# ESP_PGMRm.net
KiCad netlist of a schematic drawn in EAGLE
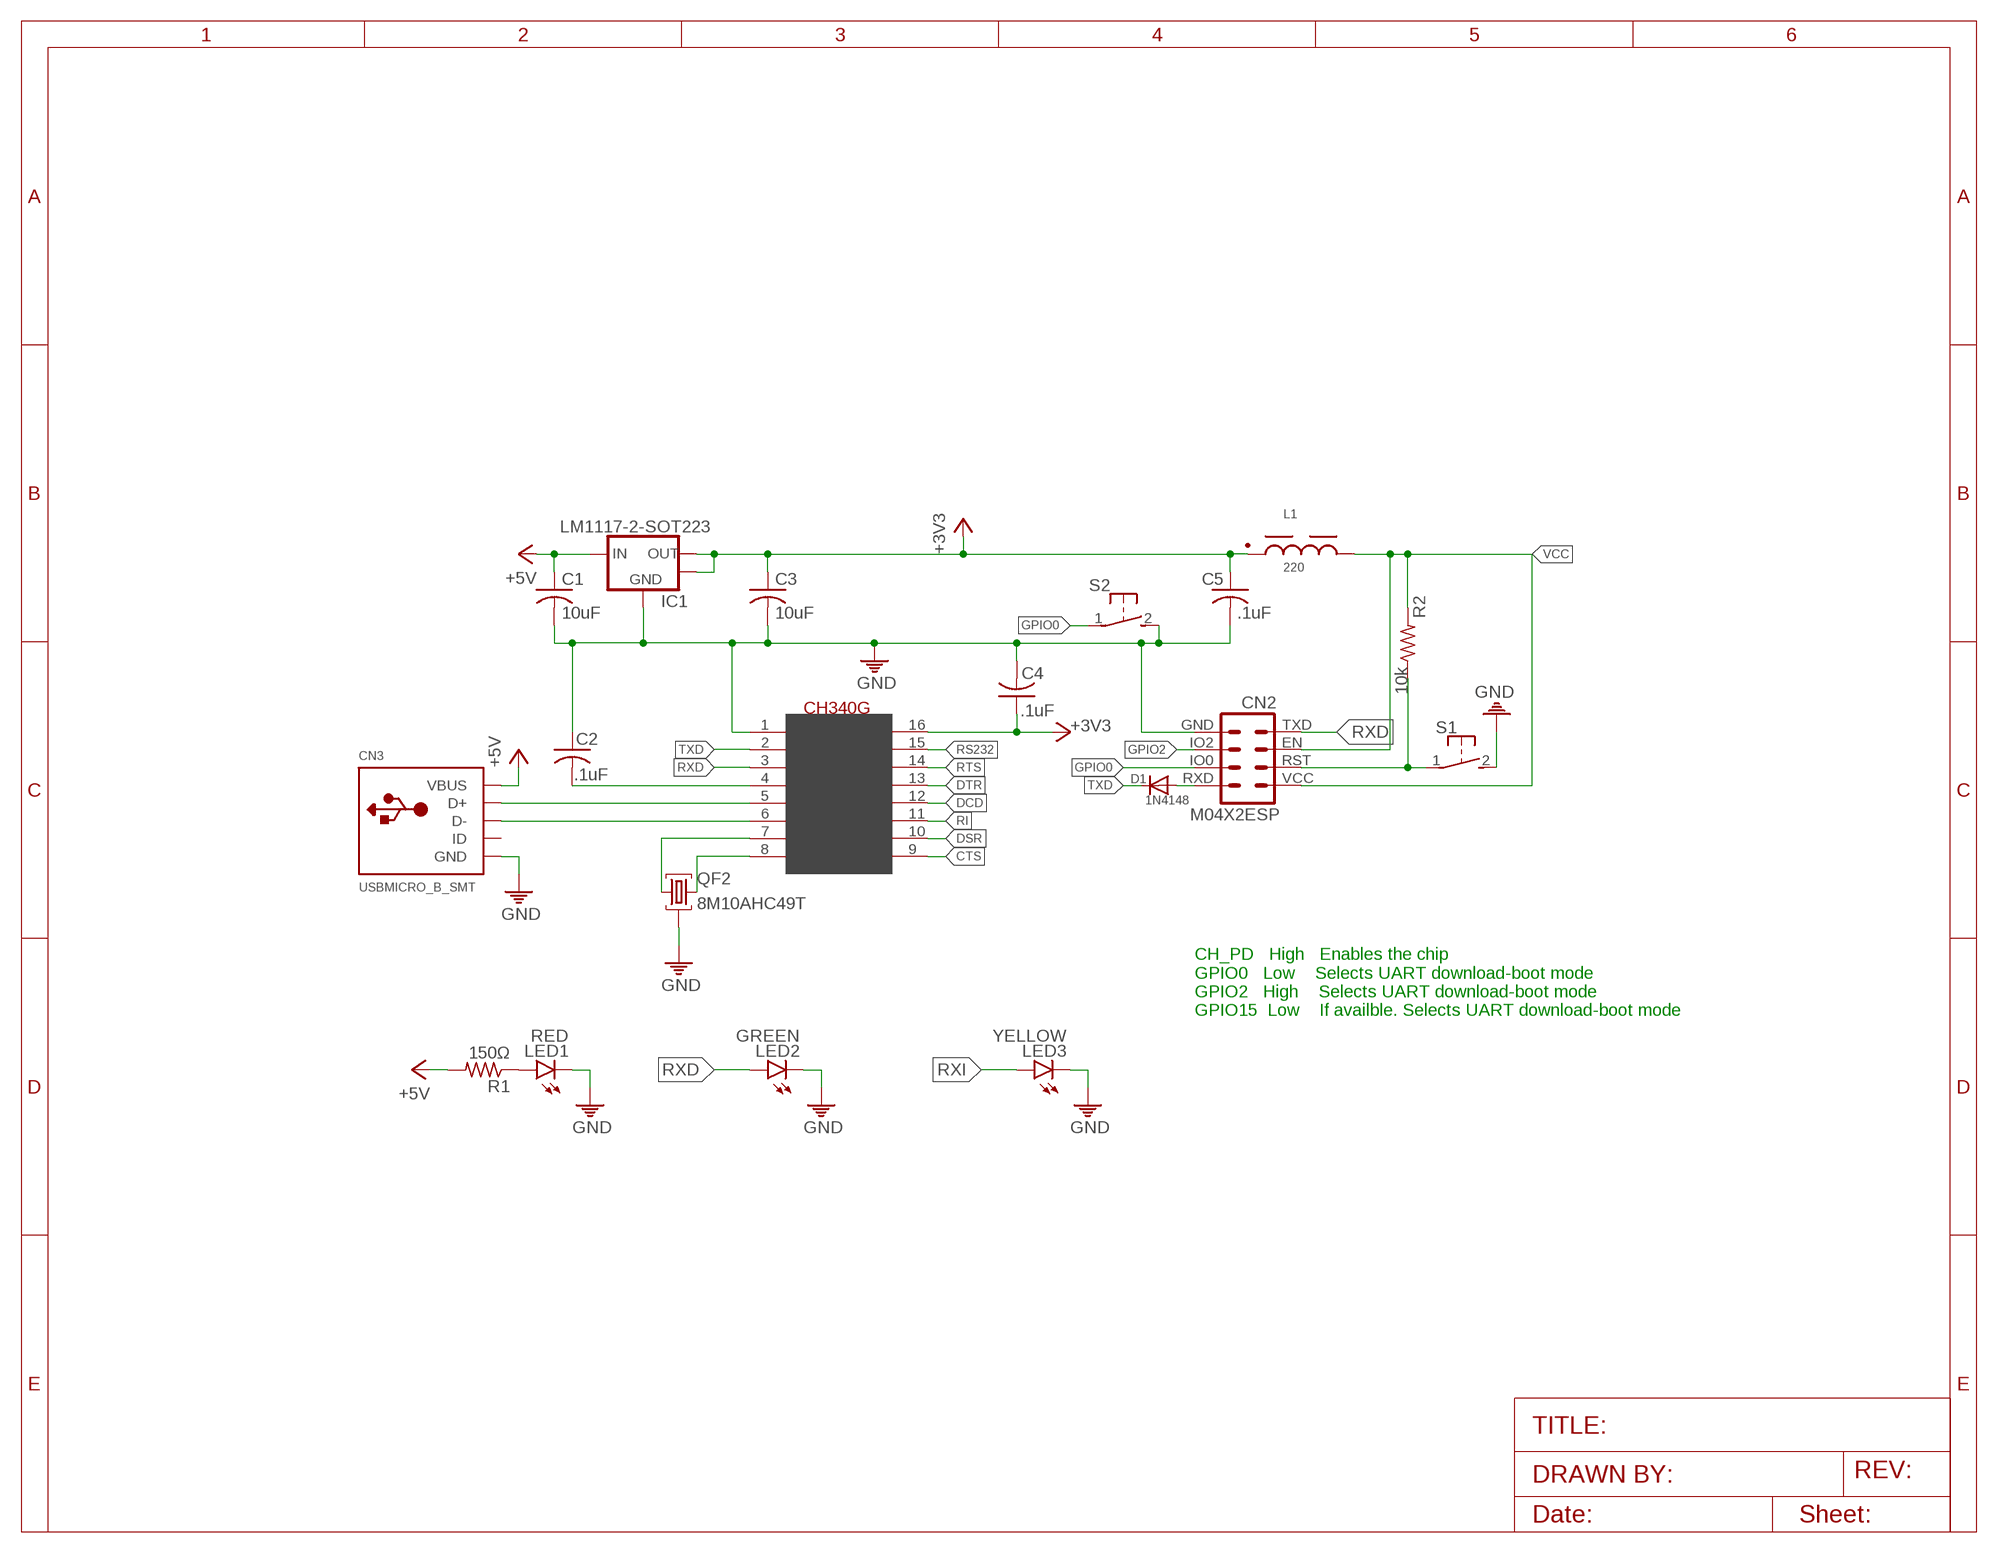
[diagram p0: schematic, sheet 1]

(export (version "E")
  (design (tool "Eeschema 10.0.6"))
  (components
    (comp (ref "C1")
      (value "10uF")
      (footprint "eagle-import:C0805")
      (libsource (lib "eagle-import") (part "C-USC0805"))
    )
    (comp (ref "C2")
      (value ".1uF")
      (footprint "eagle-import:C0805")
      (libsource (lib "eagle-import") (part "C-USC0805"))
    )
    (comp (ref "C3")
      (value "10uF")
      (footprint "eagle-import:C0805")
      (libsource (lib "eagle-import") (part "C-USC0805"))
    )
    (comp (ref "C4")
      (value ".1uF")
      (footprint "eagle-import:C0805")
      (libsource (lib "eagle-import") (part "C-USC0805"))
    )
    (comp (ref "C5")
      (value ".1uF")
      (footprint "eagle-import:C0805")
      (libsource (lib "eagle-import") (part "C-USC0805"))
    )
    (comp (ref "CN2")
      (value "M04X2ESP")
      (footprint "eagle-import:2X04-ESP")
      (libsource (lib "eagle-import") (part "M04X2ESP"))
    )
    (comp (ref "CN3")
      (value "USBMICRO_B_SMT")
      (footprint "eagle-import:USB_MICRO_B_MID")
      (libsource (lib "eagle-import") (part "USBMICRO_B_SMT"))
    )
    (comp (ref "D1")
      (value "1N4148")
      (footprint "eagle-import:SOD-123")
      (libsource (lib "eagle-import") (part "DIODE_SOD-123"))
    )
    (comp (ref "IC1")
      (value "LM1117-2-SOT223")
      (footprint "eagle-import:SOT-223-3")
      (libsource (lib "eagle-import") (part "LM1117-2-SOT223"))
    )
    (comp (ref "IC2")
      (value "CH340G")
      (footprint "eagle-import:SOIC16")
      (libsource (lib "eagle-import") (part "CH340G"))
    )
    (comp (ref "L1")
      (value "220")
      (footprint "eagle-import:WE-CBA_0805(W=3)")
      (libsource (lib "eagle-import") (part "WE-CBA_0805_WB/HS_782851102"))
    )
    (comp (ref "LED1")
      (value "RED")
      (footprint "eagle-import:CHIPLED_1206")
      (libsource (lib "eagle-import") (part "LEDCHIPLED_1206"))
    )
    (comp (ref "LED2")
      (value "GREEN")
      (footprint "eagle-import:CHIPLED_1206")
      (libsource (lib "eagle-import") (part "LEDCHIPLED_1206"))
    )
    (comp (ref "LED3")
      (value "YELLOW")
      (footprint "eagle-import:CHIPLED_1206")
      (libsource (lib "eagle-import") (part "LEDCHIPLED_1206"))
    )
    (comp (ref "QF2")
      (value "8M10AHC49T")
      (footprint "eagle-import:HC49U")
      (libsource (lib "eagle-import") (part "8M10AHC49T"))
    )
    (comp (ref "R1")
      (value "150Ω")
      (footprint "eagle-import:M0805")
      (libsource (lib "eagle-import") (part "resistor_348_R-US_M0805"))
    )
    (comp (ref "R2")
      (value "10k")
      (footprint "eagle-import:R0805")
      (libsource (lib "eagle-import") (part "R-US_R0805"))
    )
    (comp (ref "S1")
      (value "MOMENTARY-SWITCH-SPST-PTH-6.0X6.0-5MM")
      (footprint "eagle-import:TACTILE_SWITCH_PTH_6.0X6.0-5MM")
      (libsource (lib "eagle-import") (part "MOMENTARY-SWITCH-SPST-PTH-6.0X6.0-5MM"))
    )
    (comp (ref "S2")
      (value "MOMENTARY-SWITCH-SPST-PTH-6.0X6.0-5MM")
      (footprint "eagle-import:TACTILE_SWITCH_PTH_6.0X6.0-5MM")
      (libsource (lib "eagle-import") (part "MOMENTARY-SWITCH-SPST-PTH-6.0X6.0-5MM"))
    )
  )
  (nets
    (net (code "1") (name "+3V3") (class "Default")
      (node (ref "C3") (pin "1") (pinfunction "1_1") (pintype "passive"))
      (node (ref "C4") (pin "1") (pinfunction "1_1") (pintype "passive"))
      (node (ref "C5") (pin "1") (pinfunction "1_1") (pintype "passive"))
      (node (ref "IC1") (pin "2") (pinfunction "VOUT_2") (pintype "bidirectional"))
      (node (ref "IC1") (pin "4") (pinfunction "HEATSINK_4") (pintype "bidirectional"))
      (node (ref "IC2") (pin "16") (pinfunction "VCC_16") (pintype "bidirectional"))
      (node (ref "L1") (pin "1") (pinfunction "1_1") (pintype "passive"))
    )
    (net (code "2") (name "+5V") (class "Default")
      (node (ref "C1") (pin "1") (pinfunction "1_1") (pintype "passive"))
      (node (ref "CN3") (pin "VBUS") (pinfunction "VBUS_VBUS") (pintype "power_in"))
      (node (ref "IC1") (pin "3") (pinfunction "VIN_3") (pintype "bidirectional"))
      (node (ref "R1") (pin "2") (pinfunction "2_2") (pintype "passive"))
    )
    (net (code "3") (name "CTS") (class "Default")
      (node (ref "IC2") (pin "9") (pinfunction "CTS_9") (pintype "bidirectional"))
    )
    (net (code "4") (name "DCD") (class "Default")
      (node (ref "IC2") (pin "12") (pinfunction "DCD_12") (pintype "bidirectional"))
    )
    (net (code "5") (name "DSR") (class "Default")
      (node (ref "IC2") (pin "10") (pinfunction "DSR_10") (pintype "bidirectional"))
    )
    (net (code "6") (name "DTR") (class "Default")
      (node (ref "IC2") (pin "13") (pinfunction "DTR_13") (pintype "bidirectional"))
    )
    (net (code "7") (name "GND") (class "Default")
      (node (ref "C1") (pin "2") (pinfunction "2_2") (pintype "passive"))
      (node (ref "C2") (pin "1") (pinfunction "1_1") (pintype "passive"))
      (node (ref "C3") (pin "2") (pinfunction "2_2") (pintype "passive"))
      (node (ref "C4") (pin "2") (pinfunction "2_2") (pintype "passive"))
      (node (ref "C5") (pin "2") (pinfunction "2_2") (pintype "passive"))
      (node (ref "CN2") (pin "GND") (pinfunction "1_GND") (pintype "passive"))
      (node (ref "CN3") (pin "GND") (pinfunction "GND_GND") (pintype "power_in"))
      (node (ref "IC1") (pin "1") (pinfunction "GND_1") (pintype "bidirectional"))
      (node (ref "IC2") (pin "1") (pinfunction "GND_1") (pintype "bidirectional"))
      (node (ref "LED1") (pin "C") (pinfunction "C_C") (pintype "passive"))
      (node (ref "LED2") (pin "C") (pinfunction "C_C") (pintype "passive"))
      (node (ref "LED3") (pin "C") (pinfunction "C_C") (pintype "passive"))
      (node (ref "QF2") (pin "2") (pinfunction "2_2") (pintype "passive"))
      (node (ref "S1") (pin "2") (pinfunction "S_2") (pintype "passive"))
      (node (ref "S2") (pin "2") (pinfunction "S_2") (pintype "passive"))
    )
    (net (code "8") (name "GPIO0") (class "Default")
      (node (ref "CN2") (pin "IO0") (pinfunction "3_IO0") (pintype "passive"))
      (node (ref "S2") (pin "1") (pinfunction "P_1") (pintype "passive"))
    )
    (net (code "9") (name "GPIO2") (class "Default")
      (node (ref "CN2") (pin "IO2") (pinfunction "2_IO2") (pintype "passive"))
    )
    (net (code "10") (name "Net-(CN2-7)") (class "Default")
      (node (ref "CN2") (pin "RST") (pinfunction "7_RST") (pintype "passive"))
      (node (ref "R2") (pin "1") (pinfunction "1_1") (pintype "passive"))
      (node (ref "S1") (pin "1") (pinfunction "P_1") (pintype "passive"))
    )
    (net (code "11") (name "Net-(IC2-D+)") (class "Default")
      (node (ref "CN3") (pin "D+") (pinfunction "D+_D+") (pintype "bidirectional"))
      (node (ref "IC2") (pin "5") (pinfunction "D+_5") (pintype "bidirectional"))
    )
    (net (code "12") (name "Net-(IC2-D-)") (class "Default")
      (node (ref "CN3") (pin "D-") (pinfunction "D-_D-") (pintype "bidirectional"))
      (node (ref "IC2") (pin "6") (pinfunction "D-_6") (pintype "bidirectional"))
    )
    (net (code "13") (name "Net-(IC2-V3)") (class "Default")
      (node (ref "C2") (pin "2") (pinfunction "2_2") (pintype "passive"))
      (node (ref "IC2") (pin "4") (pinfunction "V3_4") (pintype "bidirectional"))
    )
    (net (code "14") (name "Net-(IC2-XI)") (class "Default")
      (node (ref "IC2") (pin "7") (pinfunction "XI_7") (pintype "bidirectional"))
      (node (ref "QF2") (pin "1") (pinfunction "1_1") (pintype "passive"))
    )
    (net (code "15") (name "Net-(IC2-XO)") (class "Default")
      (node (ref "IC2") (pin "8") (pinfunction "XO_8") (pintype "bidirectional"))
      (node (ref "QF2") (pin "3") (pinfunction "3_3") (pintype "passive"))
    )
    (net (code "16") (name "Net-(LED1-PadA)") (class "Default")
      (node (ref "LED1") (pin "A") (pinfunction "A_A") (pintype "passive"))
      (node (ref "R1") (pin "1") (pinfunction "1_1") (pintype "passive"))
    )
    (net (code "17") (name "RI") (class "Default")
      (node (ref "IC2") (pin "11") (pinfunction "RI_11") (pintype "bidirectional"))
    )
    (net (code "18") (name "RS232") (class "Default")
      (node (ref "IC2") (pin "15") (pinfunction "RS232_15") (pintype "bidirectional"))
    )
    (net (code "19") (name "RTS") (class "Default")
      (node (ref "IC2") (pin "14") (pinfunction "RTS_14") (pintype "bidirectional"))
    )
    (net (code "20") (name "RXD") (class "Default")
      (node (ref "CN2") (pin "TXD") (pinfunction "5_TXD") (pintype "passive"))
      (node (ref "IC2") (pin "3") (pinfunction "RX_3") (pintype "bidirectional"))
      (node (ref "LED2") (pin "A") (pinfunction "A_A") (pintype "passive"))
    )
    (net (code "21") (name "RXI") (class "Default")
      (node (ref "CN2") (pin "RXD") (pinfunction "4_RXD") (pintype "passive"))
      (node (ref "D1") (pin "A") (pinfunction "A_A") (pintype "passive"))
      (node (ref "LED3") (pin "A") (pinfunction "A_A") (pintype "passive"))
    )
    (net (code "22") (name "TXD") (class "Default")
      (node (ref "D1") (pin "C") (pinfunction "C_C") (pintype "passive"))
      (node (ref "IC2") (pin "2") (pinfunction "TX_2") (pintype "bidirectional"))
    )
    (net (code "23") (name "VCC") (class "Default")
      (node (ref "CN2") (pin "EN") (pinfunction "6_EN") (pintype "passive"))
      (node (ref "CN2") (pin "VCC") (pinfunction "8_VCC") (pintype "passive"))
      (node (ref "L1") (pin "2") (pinfunction "2_2") (pintype "passive"))
      (node (ref "R2") (pin "2") (pinfunction "2_2") (pintype "passive"))
    )
    (net (code "24") (name "unconnected-(CN3-PadID)") (class "Default")
      (node (ref "CN3") (pin "ID") (pinfunction "ID_ID") (pintype "bidirectional"))
    )
  )
)
